# Adafruit_EMC2101.net
KiCad netlist of a schematic drawn in EAGLE
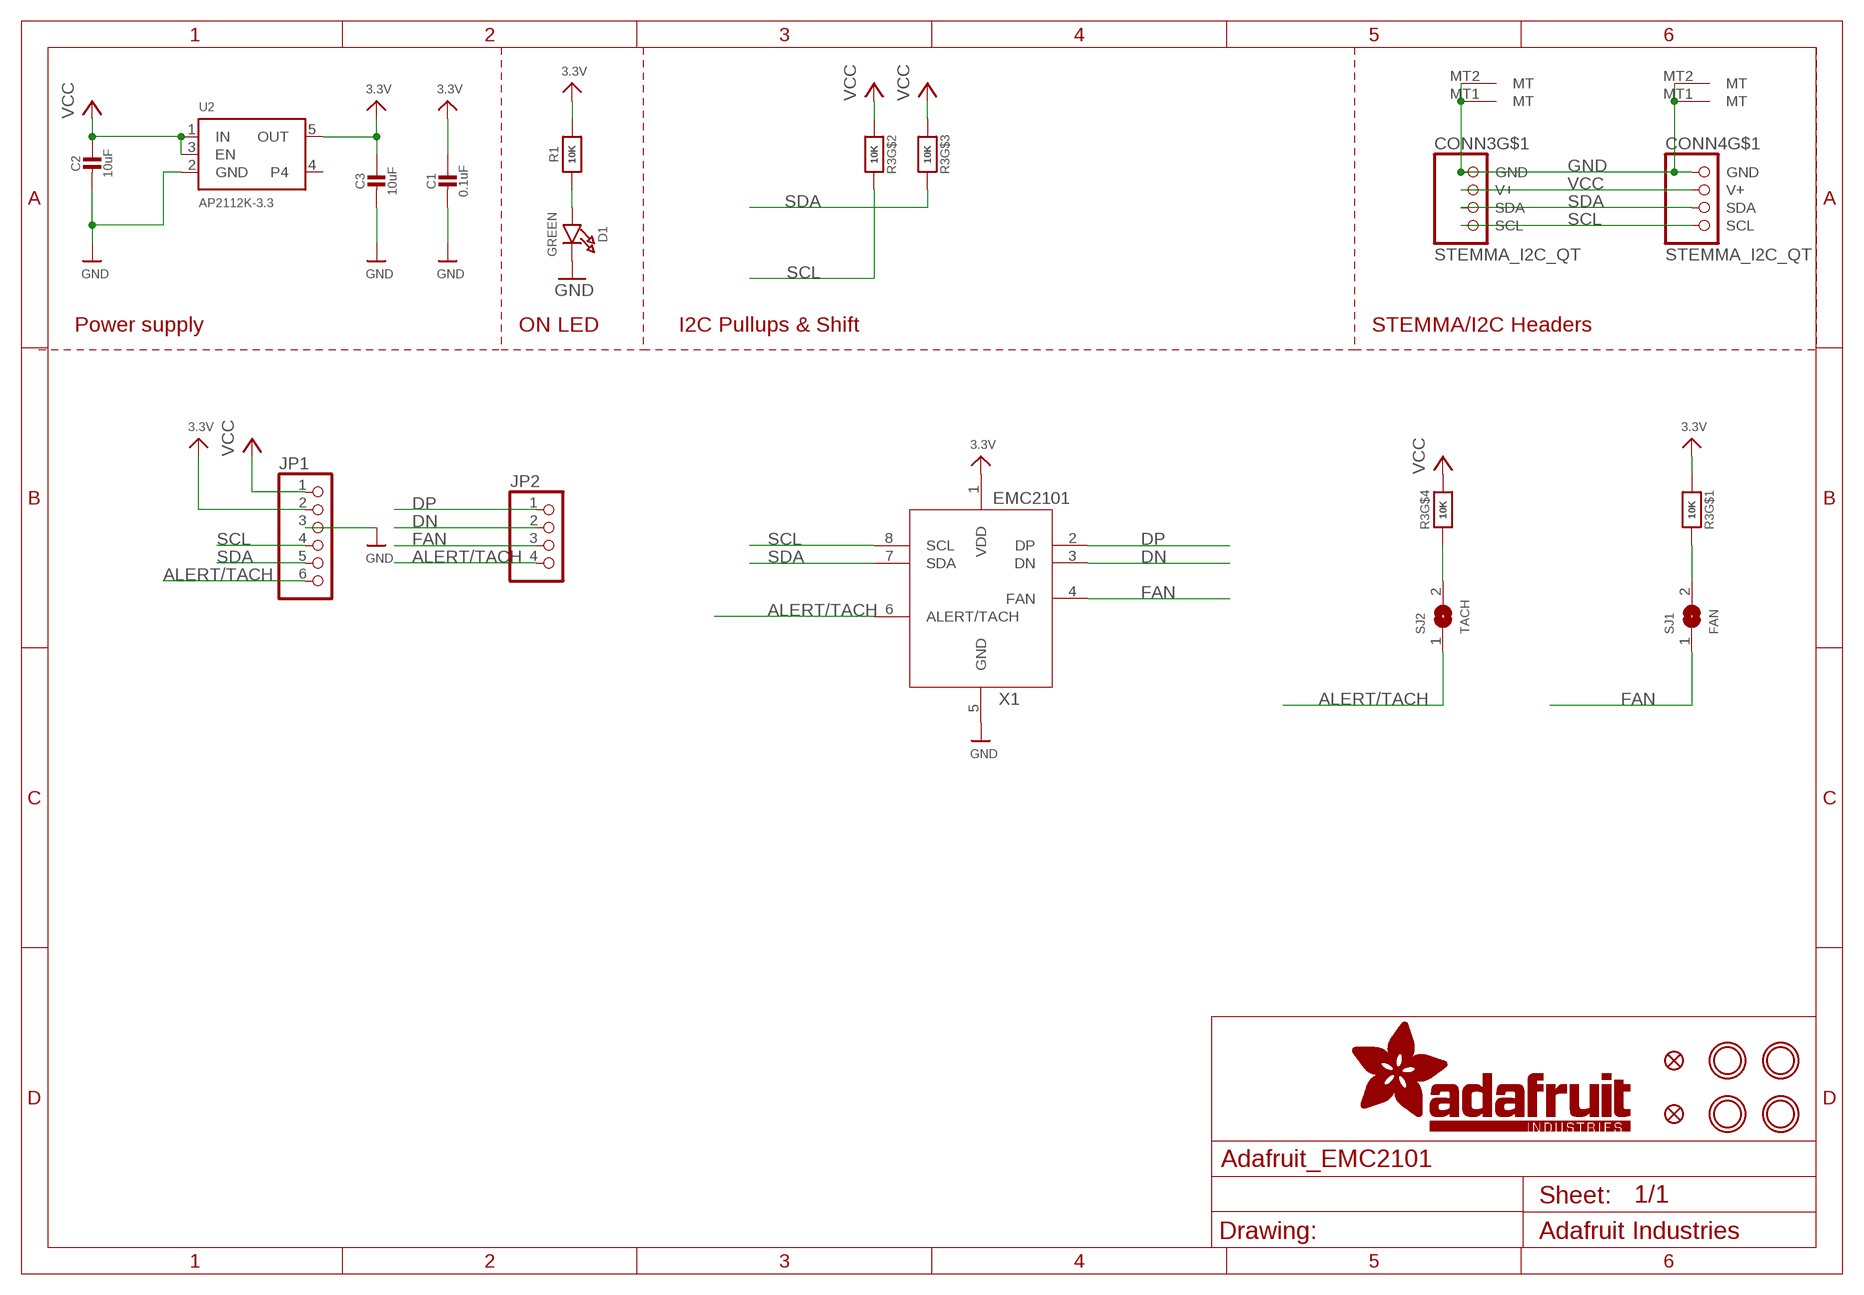
[diagram p0: schematic, sheet 1]

(export (version "E")
  (design (tool "Eeschema 10.0.6"))
  (components
    (comp (ref "C1")
      (value "0.1uF")
      (footprint "eagle-import:0603-NO")
      (libsource (lib "eagle-import") (part "CAP_CERAMIC0603_NO"))
    )
    (comp (ref "C2")
      (value "10uF")
      (footprint "eagle-import:0805-NO")
      (libsource (lib "eagle-import") (part "CAP_CERAMIC0805-NOOUTLINE"))
    )
    (comp (ref "C3")
      (value "10uF")
      (footprint "eagle-import:0805-NO")
      (libsource (lib "eagle-import") (part "CAP_CERAMIC0805-NOOUTLINE"))
    )
    (comp (ref "CONN3")
      (value "STEMMA_I2C_QT")
      (footprint "eagle-import:JST_SH4")
      (libsource (lib "eagle-import") (part "STEMMA_I2C_QT"))
    )
    (comp (ref "CONN4")
      (value "STEMMA_I2C_QT")
      (footprint "eagle-import:JST_SH4")
      (libsource (lib "eagle-import") (part "STEMMA_I2C_QT"))
    )
    (comp (ref "D1")
      (value "GREEN")
      (footprint "eagle-import:CHIPLED_0603_NOOUTLINE")
      (libsource (lib "eagle-import") (part "LED0603_NOOUTLINE"))
    )
    (comp (ref "FID3")
      (value "FIDUCIAL_1MM")
      (footprint "eagle-import:FIDUCIAL_1MM")
      (libsource (lib "eagle-import") (part "FIDUCIAL_1MM"))
    )
    (comp (ref "FID4")
      (value "FIDUCIAL_1MM")
      (footprint "eagle-import:FIDUCIAL_1MM")
      (libsource (lib "eagle-import") (part "FIDUCIAL_1MM"))
    )
    (comp (ref "JP1")
      (value "HEADER-1X670MIL")
      (footprint "eagle-import:1X06_ROUND_70")
      (libsource (lib "eagle-import") (part "HEADER-1X670MIL"))
    )
    (comp (ref "JP2")
      (value "HEADER-1X4ROUND")
      (footprint "eagle-import:1X04_ROUND")
      (libsource (lib "eagle-import") (part "HEADER-1X4ROUND"))
    )
    (comp (ref "R1")
      (value "10K")
      (footprint "eagle-import:_0603MP")
      (libsource (lib "eagle-import") (part "RESISTOR_0603MP"))
    )
    (comp (ref "R3")
      (value "10K")
      (footprint "eagle-import:RESPACK_4X0603")
      (libsource (lib "eagle-import") (part "RESISTOR_4PACK"))
    )
    (comp (ref "SJ1")
      (value "FAN")
      (footprint "eagle-import:SOLDERJUMPER_CLOSEDWIRE")
      (libsource (lib "eagle-import") (part "SOLDERJUMPERCLOSED"))
    )
    (comp (ref "SJ2")
      (value "TACH")
      (footprint "eagle-import:SOLDERJUMPER_ARROW_NOPASTE")
      (libsource (lib "eagle-import") (part "SOLDERJUMPER"))
    )
    (comp (ref "U$1")
      (value "MOUNTINGHOLE2.5")
      (footprint "eagle-import:MOUNTINGHOLE_2.5_PLATED")
      (libsource (lib "eagle-import") (part "MOUNTINGHOLE2.5"))
    )
    (comp (ref "U$17")
      (value "MOUNTINGHOLE2.5")
      (footprint "eagle-import:MOUNTINGHOLE_2.5_PLATED")
      (libsource (lib "eagle-import") (part "MOUNTINGHOLE2.5"))
    )
    (comp (ref "U$19")
      (value "MOUNTINGHOLE2.5")
      (footprint "eagle-import:MOUNTINGHOLE_2.5_PLATED")
      (libsource (lib "eagle-import") (part "MOUNTINGHOLE2.5"))
    )
    (comp (ref "U$21")
      (value "MOUNTINGHOLE2.5")
      (footprint "eagle-import:MOUNTINGHOLE_2.5_PLATED")
      (libsource (lib "eagle-import") (part "MOUNTINGHOLE2.5"))
    )
    (comp (ref "U2")
      (value "AP2112K-3.3")
      (footprint "eagle-import:SOT23-5")
      (libsource (lib "eagle-import") (part "VREG_SOT23-5"))
    )
    (comp (ref "X1")
      (value "EMC2101-AZCL")
      (footprint "eagle-import:MSOP8_0.65MM")
      (libsource (lib "eagle-import") (part "EMC2101-AZCL"))
    )
  )
  (nets
    (net (code "1") (name "/ALERT{slash}TACH") (class "Default")
      (node (ref "JP1") (pin "6") (pinfunction "6_6") (pintype "passive"))
      (node (ref "JP2") (pin "4") (pinfunction "4_4") (pintype "passive"))
      (node (ref "SJ2") (pin "1") (pinfunction "1_1") (pintype "passive"))
      (node (ref "X1") (pin "6") (pinfunction "ALERT/TACH_6") (pintype "bidirectional"))
    )
    (net (code "2") (name "/DN") (class "Default")
      (node (ref "JP2") (pin "2") (pinfunction "2_2") (pintype "passive"))
      (node (ref "X1") (pin "3") (pinfunction "DN_3") (pintype "input"))
    )
    (net (code "3") (name "/DP") (class "Default")
      (node (ref "JP2") (pin "1") (pinfunction "1_1") (pintype "passive"))
      (node (ref "X1") (pin "2") (pinfunction "DP_2") (pintype "input"))
    )
    (net (code "4") (name "/FAN") (class "Default")
      (node (ref "JP2") (pin "3") (pinfunction "3_3") (pintype "passive"))
      (node (ref "SJ1") (pin "1") (pinfunction "1_1") (pintype "passive"))
      (node (ref "X1") (pin "4") (pinfunction "FAN_4") (pintype "output"))
    )
    (net (code "5") (name "/SCL") (class "Default")
      (node (ref "CONN3") (pin "4") (pinfunction "SCL_4") (pintype "passive"))
      (node (ref "CONN4") (pin "4") (pinfunction "SCL_4") (pintype "passive"))
      (node (ref "JP1") (pin "4") (pinfunction "4_4") (pintype "passive"))
      (node (ref "R3") (pin "7") (pinfunction "2_7") (pintype "passive"))
      (node (ref "X1") (pin "8") (pinfunction "SCL_8") (pintype "bidirectional"))
    )
    (net (code "6") (name "/SDA") (class "Default")
      (node (ref "CONN3") (pin "3") (pinfunction "SDA_3") (pintype "passive"))
      (node (ref "CONN4") (pin "3") (pinfunction "SDA_3") (pintype "passive"))
      (node (ref "JP1") (pin "5") (pinfunction "5_5") (pintype "passive"))
      (node (ref "R3") (pin "6") (pinfunction "2_6") (pintype "passive"))
      (node (ref "X1") (pin "7") (pinfunction "SDA_7") (pintype "bidirectional"))
    )
    (net (code "7") (name "3.3V") (class "Default")
      (node (ref "C1") (pin "1") (pinfunction "1_1") (pintype "passive"))
      (node (ref "C3") (pin "1") (pinfunction "1_1") (pintype "passive"))
      (node (ref "JP1") (pin "2") (pinfunction "2_2") (pintype "passive"))
      (node (ref "R1") (pin "2") (pinfunction "2_2") (pintype "passive"))
      (node (ref "R3") (pin "1") (pinfunction "1_1") (pintype "passive"))
      (node (ref "U2") (pin "5") (pinfunction "OUT_5") (pintype "power_in"))
      (node (ref "X1") (pin "1") (pinfunction "VDD_1") (pintype "power_in"))
    )
    (net (code "8") (name "GND") (class "Default")
      (node (ref "C1") (pin "2") (pinfunction "2_2") (pintype "passive"))
      (node (ref "C2") (pin "2") (pinfunction "2_2") (pintype "passive"))
      (node (ref "C3") (pin "2") (pinfunction "2_2") (pintype "passive"))
      (node (ref "CONN3") (pin "1") (pinfunction "GND_1") (pintype "passive"))
      (node (ref "CONN3") (pin "MT1") (pinfunction "MT_MT1") (pintype "bidirectional"))
      (node (ref "CONN3") (pin "MT2") (pinfunction "MT_MT2") (pintype "bidirectional"))
      (node (ref "CONN4") (pin "1") (pinfunction "GND_1") (pintype "passive"))
      (node (ref "CONN4") (pin "MT1") (pinfunction "MT_MT1") (pintype "bidirectional"))
      (node (ref "CONN4") (pin "MT2") (pinfunction "MT_MT2") (pintype "bidirectional"))
      (node (ref "D1") (pin "C") (pinfunction "C_C") (pintype "passive"))
      (node (ref "JP1") (pin "3") (pinfunction "3_3") (pintype "passive"))
      (node (ref "U2") (pin "2") (pinfunction "GND_2") (pintype "power_in"))
      (node (ref "X1") (pin "5") (pinfunction "GND_5") (pintype "power_in"))
    )
    (net (code "9") (name "Net-(D1-PadA)") (class "Default")
      (node (ref "D1") (pin "A") (pinfunction "A_A") (pintype "passive"))
      (node (ref "R1") (pin "1") (pinfunction "1_1") (pintype "passive"))
    )
    (net (code "10") (name "Net-(R3A-2)") (class "Default")
      (node (ref "R3") (pin "8") (pinfunction "2_8") (pintype "passive"))
      (node (ref "SJ1") (pin "2") (pinfunction "2_2") (pintype "passive"))
    )
    (net (code "11") (name "Net-(R3D-1)") (class "Default")
      (node (ref "R3") (pin "4") (pinfunction "1_4") (pintype "passive"))
      (node (ref "SJ2") (pin "2") (pinfunction "2_2") (pintype "passive"))
    )
    (net (code "12") (name "VCC") (class "Default")
      (node (ref "C2") (pin "1") (pinfunction "1_1") (pintype "passive"))
      (node (ref "CONN3") (pin "2") (pinfunction "V+_2") (pintype "passive"))
      (node (ref "CONN4") (pin "2") (pinfunction "V+_2") (pintype "passive"))
      (node (ref "JP1") (pin "1") (pinfunction "1_1") (pintype "passive"))
      (node (ref "R3") (pin "2") (pinfunction "1_2") (pintype "passive"))
      (node (ref "R3") (pin "3") (pinfunction "1_3") (pintype "passive"))
      (node (ref "R3") (pin "5") (pinfunction "2_5") (pintype "passive"))
      (node (ref "U2") (pin "1") (pinfunction "IN_1") (pintype "power_in"))
      (node (ref "U2") (pin "3") (pinfunction "EN_3") (pintype "input"))
    )
    (net (code "13") (name "unconnected-(U2-P4-Pad4)") (class "Default")
      (node (ref "U2") (pin "4") (pinfunction "P4_4") (pintype "bidirectional"))
    )
  )
)
